# optMotorButtonBoard.net
KiCad netlist of a schematic drawn in EAGLE
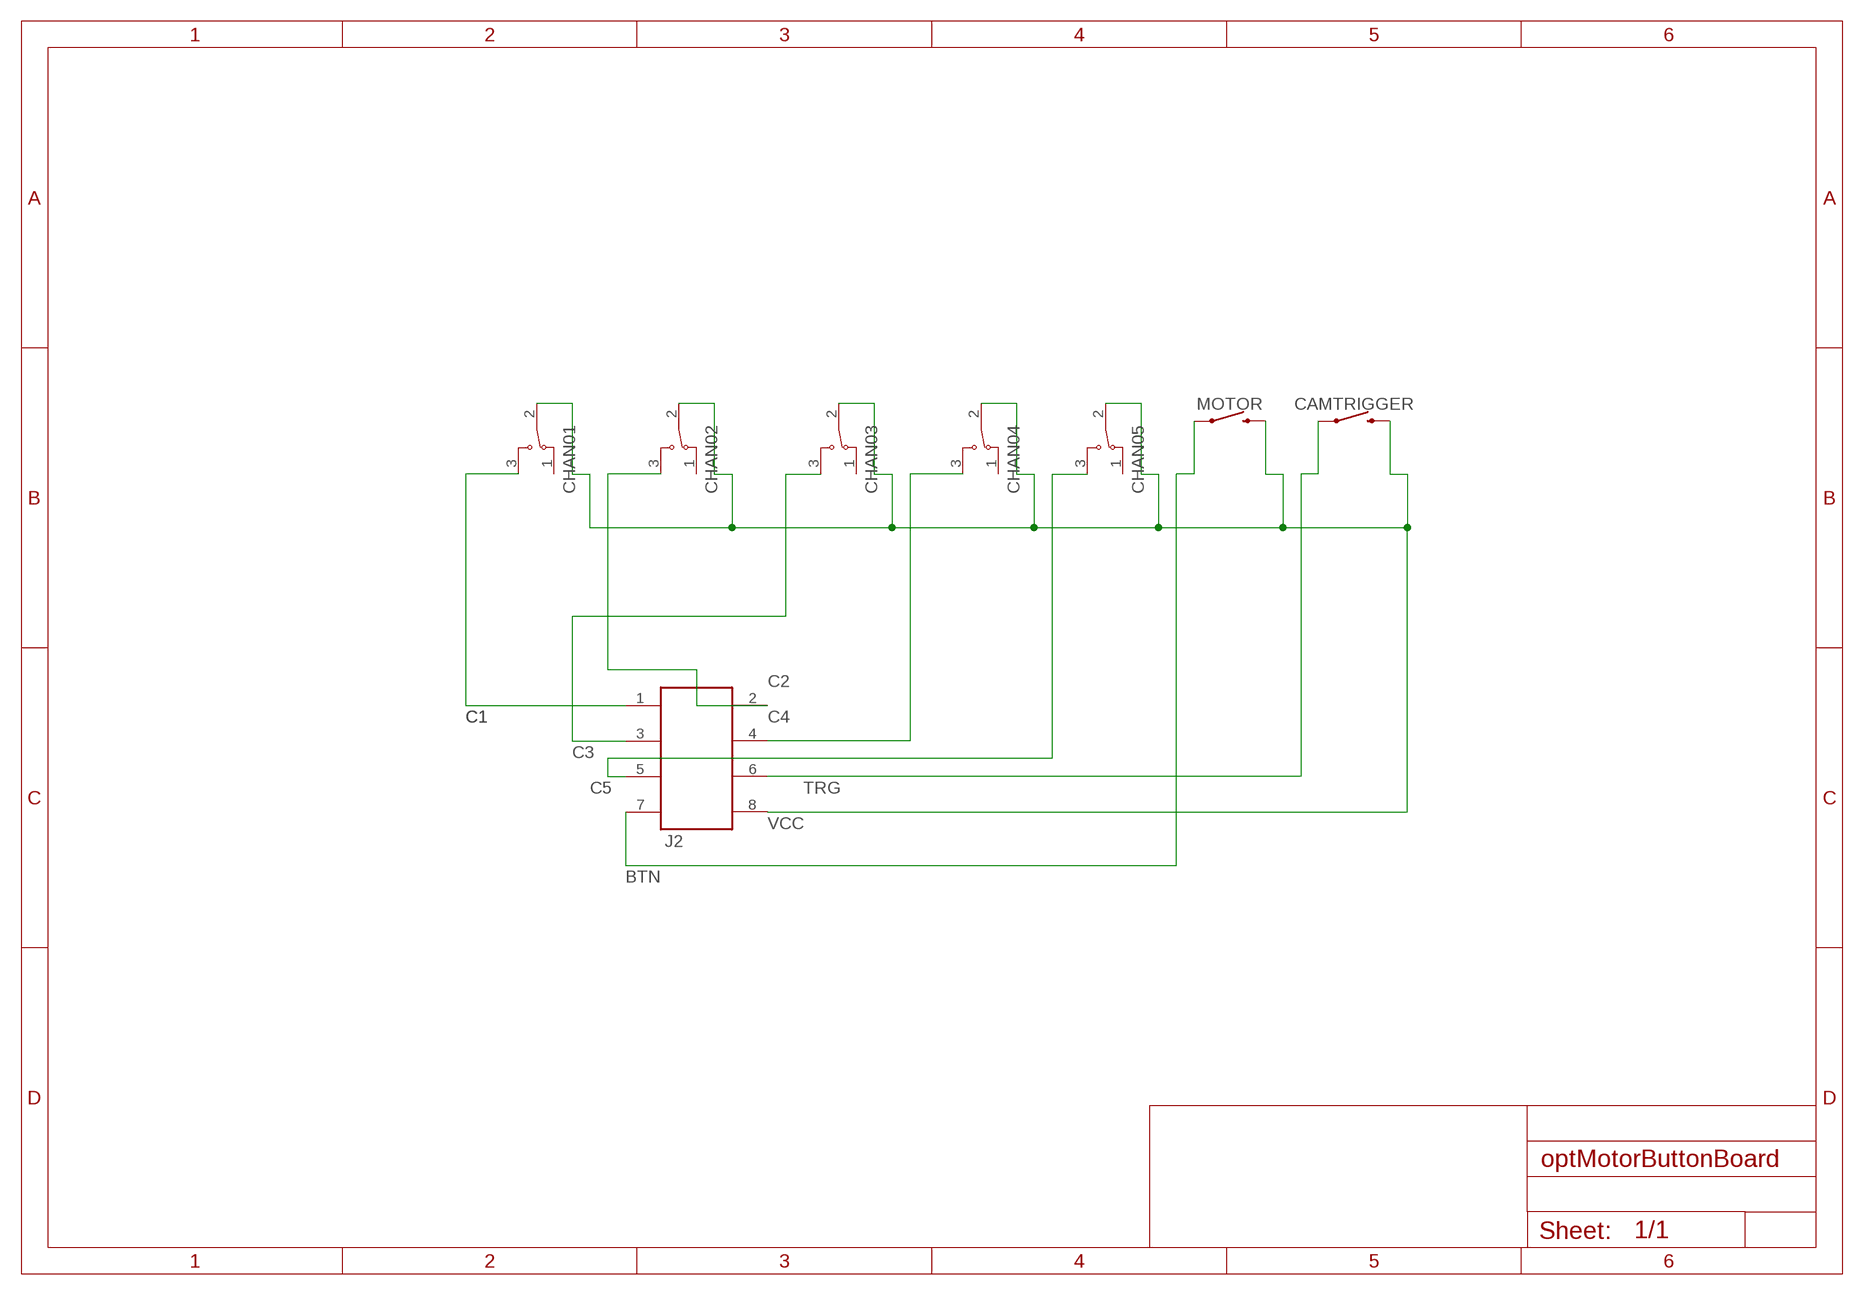
[diagram p0: schematic, sheet 1]

(export (version "E")
  (design (tool "Eeschema 10.0.6"))
  (components
    (comp (ref "CAMTRIGGER")
      (value "MOMENTARY-SWITCH-SPST-PTH-12MM")
      (footprint "eagle-import:TACTILE_SWITCH_PTH_12MM")
      (libsource (lib "eagle-import") (part "MOMENTARY-SWITCH-SPST-PTH-12MM"))
    )
    (comp (ref "CHAN01")
      (value "ATE1E-2M3-10-Z")
      (footprint "eagle-import:ATE1E-2M3-10-Z")
      (fields
        (field (name "DIGIKEY_PARTNO") "563-1159-ND")
        (field (name "MANUFACTURER") "Nidec Copal Electronics")
        (field (name "CREATED_BY") "PCBLayout.com")
      )
      (libsource (lib "eagle-import") (part "ATE1E-2M3-10-Z"))
    )
    (comp (ref "CHAN02")
      (value "ATE1E-2M3-10-Z")
      (footprint "eagle-import:ATE1E-2M3-10-Z")
      (fields
        (field (name "DIGIKEY_PARTNO") "563-1159-ND")
        (field (name "MANUFACTURER") "Nidec Copal Electronics")
        (field (name "CREATED_BY") "PCBLayout.com")
      )
      (libsource (lib "eagle-import") (part "ATE1E-2M3-10-Z"))
    )
    (comp (ref "CHAN03")
      (value "ATE1E-2M3-10-Z")
      (footprint "eagle-import:ATE1E-2M3-10-Z")
      (fields
        (field (name "DIGIKEY_PARTNO") "563-1159-ND")
        (field (name "MANUFACTURER") "Nidec Copal Electronics")
        (field (name "CREATED_BY") "PCBLayout.com")
      )
      (libsource (lib "eagle-import") (part "ATE1E-2M3-10-Z"))
    )
    (comp (ref "CHAN04")
      (value "ATE1E-2M3-10-Z")
      (footprint "eagle-import:ATE1E-2M3-10-Z")
      (fields
        (field (name "DIGIKEY_PARTNO") "563-1159-ND")
        (field (name "MANUFACTURER") "Nidec Copal Electronics")
        (field (name "CREATED_BY") "PCBLayout.com")
      )
      (libsource (lib "eagle-import") (part "ATE1E-2M3-10-Z"))
    )
    (comp (ref "CHAN05")
      (value "ATE1E-2M3-10-Z")
      (footprint "eagle-import:ATE1E-2M3-10-Z")
      (fields
        (field (name "DIGIKEY_PARTNO") "563-1159-ND")
        (field (name "MANUFACTURER") "Nidec Copal Electronics")
        (field (name "CREATED_BY") "PCBLayout.com")
      )
      (libsource (lib "eagle-import") (part "ATE1E-2M3-10-Z"))
    )
    (comp (ref "J2")
      (value "62400821722")
      (footprint "eagle-import:62400821722")
      (libsource (lib "eagle-import") (part "62400821722"))
    )
    (comp (ref "MOTOR")
      (value "MOMENTARY-SWITCH-SPST-PTH-12MM")
      (footprint "eagle-import:TACTILE_SWITCH_PTH_12MM")
      (libsource (lib "eagle-import") (part "MOMENTARY-SWITCH-SPST-PTH-12MM"))
    )
  )
  (nets
    (net (code "1") (name "/BTN") (class "Default")
      (node (ref "J2") (pin "7") (pinfunction "1_7") (pintype "passive"))
      (node (ref "MOTOR") (pin "1") (pinfunction "1_1") (pintype "passive"))
    )
    (net (code "2") (name "/C1") (class "Default")
      (node (ref "CHAN01") (pin "3") (pinfunction "3_3") (pintype "passive"))
      (node (ref "J2") (pin "1") (pinfunction "7_1") (pintype "passive"))
    )
    (net (code "3") (name "/C2") (class "Default")
      (node (ref "CHAN02") (pin "3") (pinfunction "3_3") (pintype "passive"))
      (node (ref "J2") (pin "2") (pinfunction "8_2") (pintype "passive"))
    )
    (net (code "4") (name "/C3") (class "Default")
      (node (ref "CHAN03") (pin "3") (pinfunction "3_3") (pintype "passive"))
      (node (ref "J2") (pin "3") (pinfunction "5_3") (pintype "passive"))
    )
    (net (code "5") (name "/C4") (class "Default")
      (node (ref "CHAN04") (pin "3") (pinfunction "3_3") (pintype "passive"))
      (node (ref "J2") (pin "4") (pinfunction "6_4") (pintype "passive"))
    )
    (net (code "6") (name "/C5") (class "Default")
      (node (ref "CHAN05") (pin "3") (pinfunction "3_3") (pintype "passive"))
      (node (ref "J2") (pin "5") (pinfunction "3_5") (pintype "passive"))
    )
    (net (code "7") (name "/TRG") (class "Default")
      (node (ref "CAMTRIGGER") (pin "1") (pinfunction "1_1") (pintype "passive"))
      (node (ref "J2") (pin "6") (pinfunction "4_6") (pintype "passive"))
    )
    (net (code "8") (name "/VCC") (class "Default")
      (node (ref "CAMTRIGGER") (pin "3") (pinfunction "2_3") (pintype "passive"))
      (node (ref "CHAN01") (pin "2") (pinfunction "2_2") (pintype "passive"))
      (node (ref "CHAN02") (pin "2") (pinfunction "2_2") (pintype "passive"))
      (node (ref "CHAN03") (pin "2") (pinfunction "2_2") (pintype "passive"))
      (node (ref "CHAN04") (pin "2") (pinfunction "2_2") (pintype "passive"))
      (node (ref "CHAN05") (pin "2") (pinfunction "2_2") (pintype "passive"))
      (node (ref "J2") (pin "8") (pinfunction "2_8") (pintype "passive"))
      (node (ref "MOTOR") (pin "3") (pinfunction "2_3") (pintype "passive"))
    )
    (net (code "9") (name "unconnected-(CHAN01-Pad1)") (class "Default")
      (node (ref "CHAN01") (pin "1") (pinfunction "1_1") (pintype "passive"))
    )
    (net (code "10") (name "unconnected-(CHAN02-Pad1)") (class "Default")
      (node (ref "CHAN02") (pin "1") (pinfunction "1_1") (pintype "passive"))
    )
    (net (code "11") (name "unconnected-(CHAN03-Pad1)") (class "Default")
      (node (ref "CHAN03") (pin "1") (pinfunction "1_1") (pintype "passive"))
    )
    (net (code "12") (name "unconnected-(CHAN04-Pad1)") (class "Default")
      (node (ref "CHAN04") (pin "1") (pinfunction "1_1") (pintype "passive"))
    )
    (net (code "13") (name "unconnected-(CHAN05-Pad1)") (class "Default")
      (node (ref "CHAN05") (pin "1") (pinfunction "1_1") (pintype "passive"))
    )
  )
)
